# LoRa.net
KiCad netlist of a schematic drawn in EAGLE
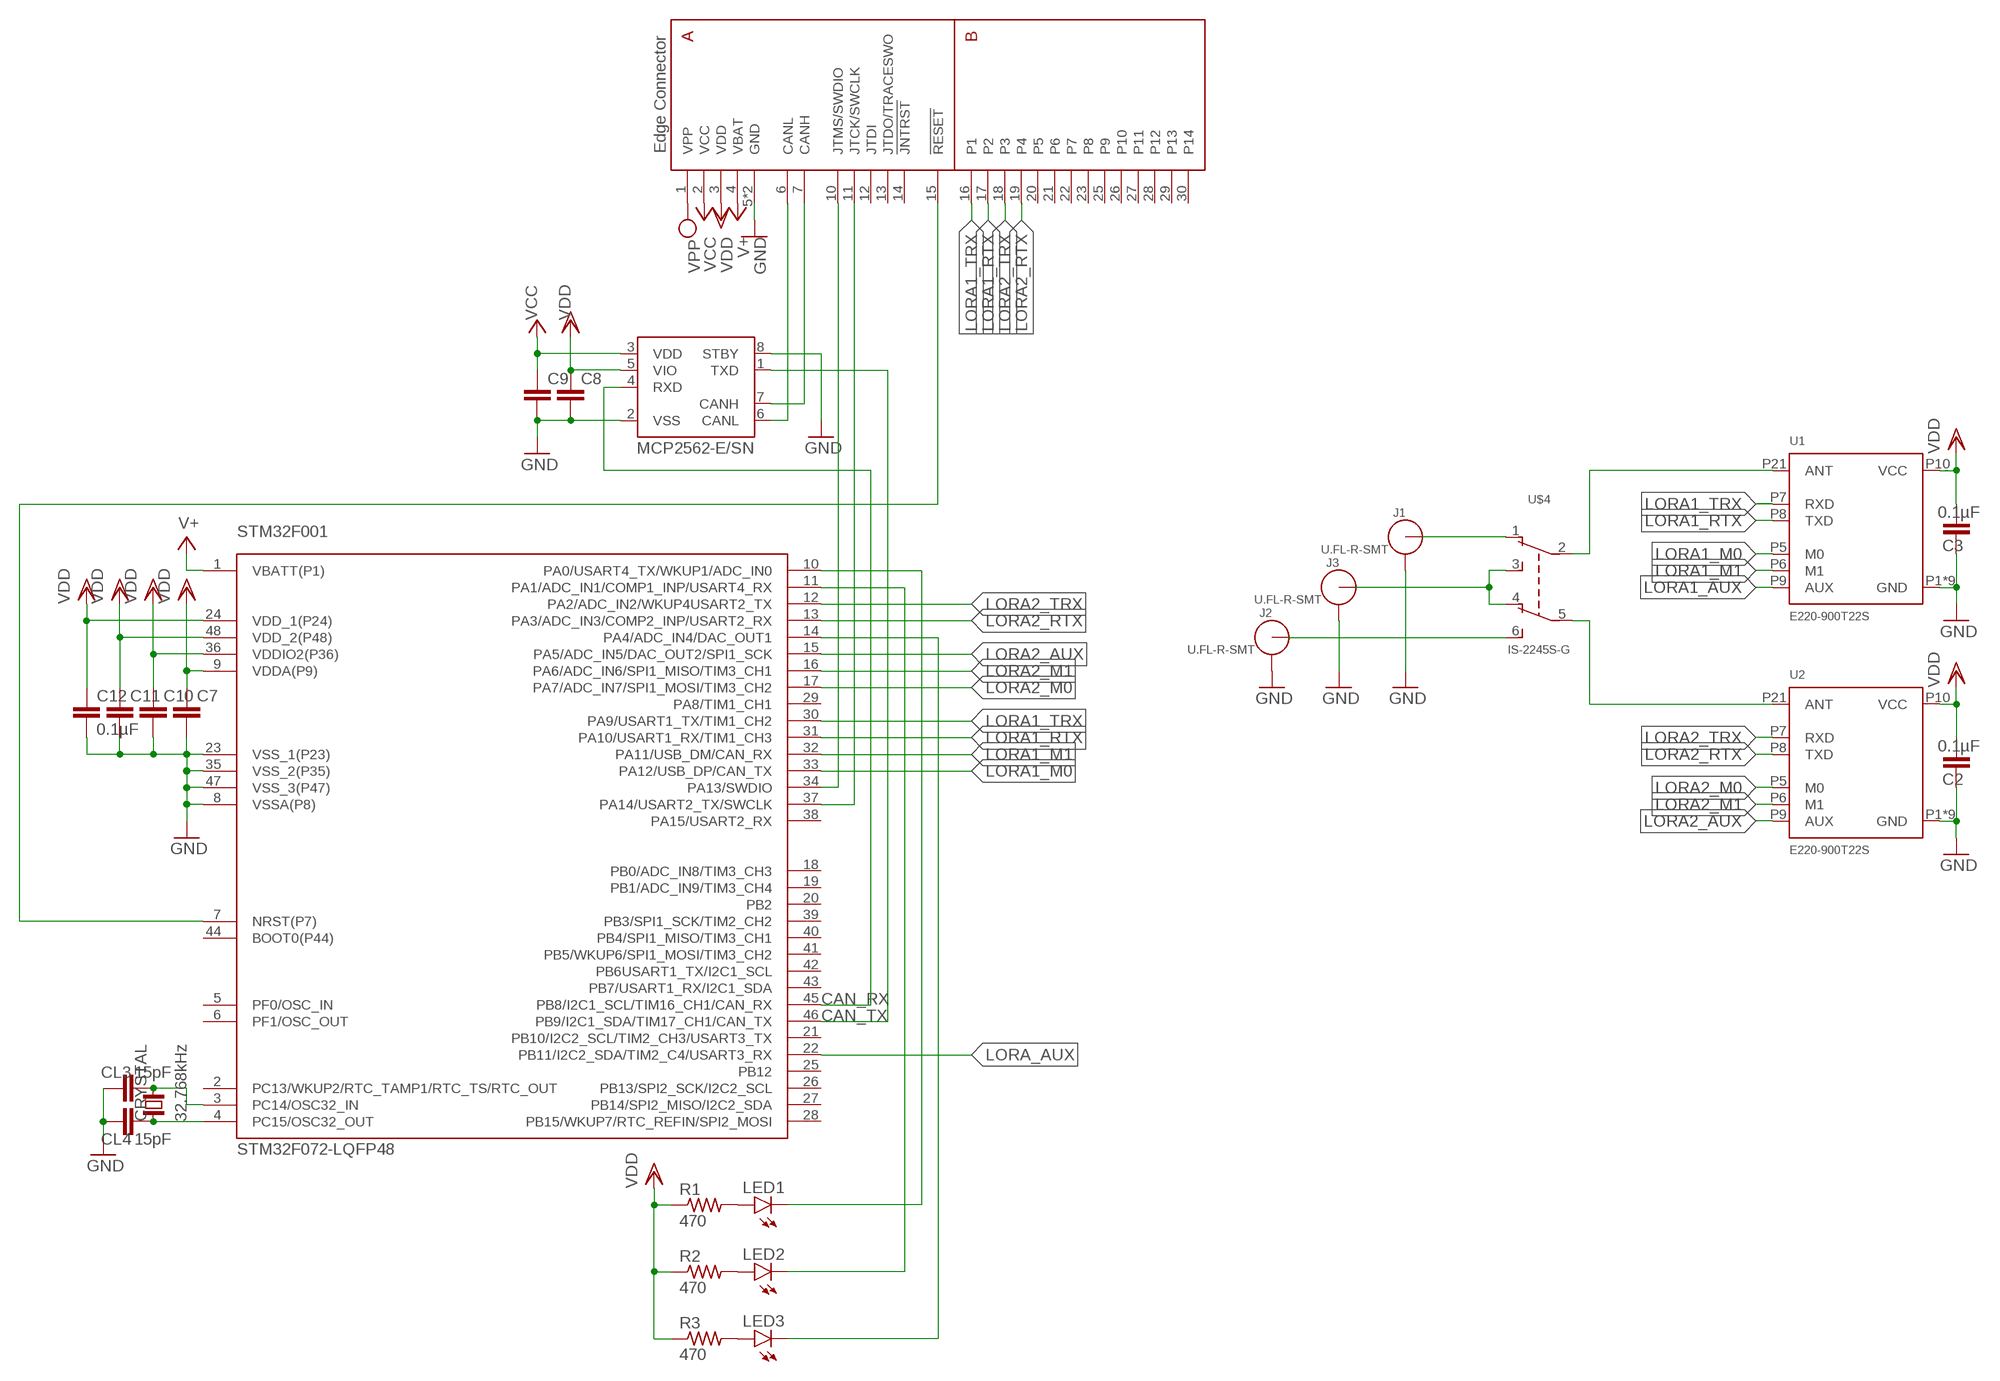
[diagram p0: schematic, sheet 1]

(export (version "E")
  (design (tool "Eeschema 10.0.6"))
  (components
    (comp (ref "C2")
      (value "0.1µF")
      (footprint "eagle-import:C0603K")
      (libsource (lib "eagle-import") (part "C-EUC0603K"))
    )
    (comp (ref "C3")
      (value "0.1µF")
      (footprint "eagle-import:C0603K")
      (libsource (lib "eagle-import") (part "C-EUC0603K"))
    )
    (comp (ref "C7")
      (value "C-EUC0603K")
      (footprint "eagle-import:C0603K")
      (libsource (lib "eagle-import") (part "C-EUC0603K"))
    )
    (comp (ref "C8")
      (value "C-EUC0603K")
      (footprint "eagle-import:C0603K")
      (libsource (lib "eagle-import") (part "C-EUC0603K"))
    )
    (comp (ref "C9")
      (value "C-EUC0603K")
      (footprint "eagle-import:C0603K")
      (libsource (lib "eagle-import") (part "C-EUC0603K"))
    )
    (comp (ref "C10")
      (value "C-EUC0603K")
      (footprint "eagle-import:C0603K")
      (libsource (lib "eagle-import") (part "C-EUC0603K"))
    )
    (comp (ref "C11")
      (value "C-EUC0603K")
      (footprint "eagle-import:C0603K")
      (libsource (lib "eagle-import") (part "C-EUC0603K"))
    )
    (comp (ref "C12")
      (value "0.1µF")
      (footprint "eagle-import:C0603K")
      (libsource (lib "eagle-import") (part "C-EUC0603K"))
    )
    (comp (ref "CL3")
      (value "15pF")
      (footprint "eagle-import:C0603K")
      (libsource (lib "eagle-import") (part "C-EUC0603K"))
    )
    (comp (ref "CL4")
      (value "15pF")
      (footprint "eagle-import:C0603K")
      (libsource (lib "eagle-import") (part "C-EUC0603K"))
    )
    (comp (ref "CRYSTAL")
      (value "32.768kHz")
      (footprint "eagle-import:FC-255")
      (libsource (lib "eagle-import") (part "CRYTALFC-255"))
    )
    (comp (ref "J1")
      (value "U.FL-R-SMT")
      (footprint "eagle-import:U.FL_SMT")
      (fields (field (name "MANUFACTURER") "Hirose") (field (name "MPN") "U.FL-R-SMT-1(01)"))
      (libsource (lib "eagle-import") (part "U.FL-R-SMT"))
    )
    (comp (ref "J2")
      (value "U.FL-R-SMT")
      (footprint "eagle-import:U.FL_SMT")
      (fields (field (name "MANUFACTURER") "Hirose") (field (name "MPN") "U.FL-R-SMT-1(01)"))
      (libsource (lib "eagle-import") (part "U.FL-R-SMT"))
    )
    (comp (ref "J3")
      (value "U.FL-R-SMT")
      (footprint "eagle-import:U.FL_SMT")
      (fields (field (name "MANUFACTURER") "Hirose") (field (name "MPN") "U.FL-R-SMT-1(01)"))
      (libsource (lib "eagle-import") (part "U.FL-R-SMT"))
    )
    (comp (ref "LED1")
      (value "LEDCHIP-LED0603")
      (footprint "eagle-import:CHIP-LED0603")
      (libsource (lib "eagle-import") (part "LEDCHIP-LED0603"))
    )
    (comp (ref "LED2")
      (value "LEDCHIP-LED0603")
      (footprint "eagle-import:CHIP-LED0603")
      (libsource (lib "eagle-import") (part "LEDCHIP-LED0603"))
    )
    (comp (ref "LED3")
      (value "LEDCHIP-LED0603")
      (footprint "eagle-import:CHIP-LED0603")
      (libsource (lib "eagle-import") (part "LEDCHIP-LED0603"))
    )
    (comp (ref "MCP1")
      (value "MCP2562-E/SN")
      (footprint "eagle-import:SOIC127P600X175-8N")
      (fields (field (name "MF") "Microchip"))
      (libsource (lib "eagle-import") (part "MCP2562-E/SN"))
    )
    (comp (ref "R1")
      (value "470")
      (footprint "eagle-import:R0603")
      (libsource (lib "eagle-import") (part "R-US_R0603"))
    )
    (comp (ref "R2")
      (value "470")
      (footprint "eagle-import:R0603")
      (libsource (lib "eagle-import") (part "R-US_R0603"))
    )
    (comp (ref "R3")
      (value "470")
      (footprint "eagle-import:R0603")
      (libsource (lib "eagle-import") (part "R-US_R0603"))
    )
    (comp (ref "STM32F001")
      (value "STM32F072-LQFP48")
      (footprint "eagle-import:LQFP48")
      (libsource (lib "eagle-import") (part "STM32F072-LQFP48"))
    )
    (comp (ref "U$2")
      (value "EDGE30")
      (footprint "eagle-import:EDGE30")
      (libsource (lib "eagle-import") (part "EDGE30"))
    )
    (comp (ref "U$4")
      (value "IS-2245S-G")
      (footprint "eagle-import:IS-2245S-G")
      (libsource (lib "eagle-import") (part "IS-2245S-G"))
    )
    (comp (ref "U1")
      (value "E220-900T22S")
      (footprint "eagle-import:E220-900T22S")
      (libsource (lib "eagle-import") (part "E220-900T22S"))
    )
    (comp (ref "U2")
      (value "E220-900T22S")
      (footprint "eagle-import:E220-900T22S")
      (libsource (lib "eagle-import") (part "E220-900T22S"))
    )
  )
  (nets
    (net (code "1") (name "/CAN_RX") (class "Default")
      (node (ref "MCP1") (pin "4") (pinfunction "RXD_4") (pintype "output"))
      (node (ref "STM32F001") (pin "45") (pinfunction "PB8/I2C1_SCL/TIM16_CH1/CAN_RX_45") (pintype "bidirectional"))
    )
    (net (code "2") (name "/CAN_TX") (class "Default")
      (node (ref "MCP1") (pin "1") (pinfunction "TXD_1") (pintype "input"))
      (node (ref "STM32F001") (pin "46") (pinfunction "PB9/I2C1_SDA/TIM17_CH1/CAN_TX_46") (pintype "bidirectional"))
    )
    (net (code "3") (name "GND") (class "Default")
      (node (ref "C10") (pin "2") (pinfunction "2_2") (pintype "passive"))
      (node (ref "C11") (pin "2") (pinfunction "2_2") (pintype "passive"))
      (node (ref "C12") (pin "2") (pinfunction "2_2") (pintype "passive"))
      (node (ref "C2") (pin "1") (pinfunction "1_1") (pintype "passive"))
      (node (ref "C3") (pin "1") (pinfunction "1_1") (pintype "passive"))
      (node (ref "C7") (pin "2") (pinfunction "2_2") (pintype "passive"))
      (node (ref "C8") (pin "2") (pinfunction "2_2") (pintype "passive"))
      (node (ref "C9") (pin "2") (pinfunction "2_2") (pintype "passive"))
      (node (ref "CL3") (pin "1") (pinfunction "1_1") (pintype "passive"))
      (node (ref "CL4") (pin "1") (pinfunction "1_1") (pintype "passive"))
      (node (ref "J1") (pin "GND1") (pinfunction "P$2_GND1") (pintype "bidirectional"))
      (node (ref "J1") (pin "GND2") (pinfunction "P$2_GND2") (pintype "bidirectional"))
      (node (ref "J2") (pin "GND1") (pinfunction "P$2_GND1") (pintype "bidirectional"))
      (node (ref "J2") (pin "GND2") (pinfunction "P$2_GND2") (pintype "bidirectional"))
      (node (ref "J3") (pin "GND1") (pinfunction "P$2_GND1") (pintype "bidirectional"))
      (node (ref "J3") (pin "GND2") (pinfunction "P$2_GND2") (pintype "bidirectional"))
      (node (ref "MCP1") (pin "2") (pinfunction "VSS_2") (pintype "power_in"))
      (node (ref "MCP1") (pin "8") (pinfunction "STBY_8") (pintype "input"))
      (node (ref "STM32F001") (pin "23") (pinfunction "VSS_1(P23)_23") (pintype "bidirectional"))
      (node (ref "STM32F001") (pin "35") (pinfunction "VSS_2(P35)_35") (pintype "bidirectional"))
      (node (ref "STM32F001") (pin "47") (pinfunction "VSS_3(P47)_47") (pintype "bidirectional"))
      (node (ref "STM32F001") (pin "8") (pinfunction "VSSA(P8)_8") (pintype "bidirectional"))
      (node (ref "U$2") (pin "5") (pinfunction "GND_5") (pintype "power_in"))
      (node (ref "U$2") (pin "8") (pinfunction "GND_8") (pintype "power_in"))
      (node (ref "U1") (pin "P1") (pinfunction "GND_P1") (pintype "bidirectional"))
      (node (ref "U1") (pin "P11") (pinfunction "GND_P11") (pintype "bidirectional"))
      (node (ref "U1") (pin "P13") (pinfunction "GND_P13") (pintype "bidirectional"))
      (node (ref "U1") (pin "P19") (pinfunction "GND_P19") (pintype "bidirectional"))
      (node (ref "U1") (pin "P2") (pinfunction "GND_P2") (pintype "bidirectional"))
      (node (ref "U1") (pin "P20") (pinfunction "GND_P20") (pintype "bidirectional"))
      (node (ref "U1") (pin "P22") (pinfunction "GND_P22") (pintype "bidirectional"))
      (node (ref "U1") (pin "P3") (pinfunction "GND_P3") (pintype "bidirectional"))
      (node (ref "U1") (pin "P4") (pinfunction "GND_P4") (pintype "bidirectional"))
      (node (ref "U2") (pin "P1") (pinfunction "GND_P1") (pintype "bidirectional"))
      (node (ref "U2") (pin "P11") (pinfunction "GND_P11") (pintype "bidirectional"))
      (node (ref "U2") (pin "P13") (pinfunction "GND_P13") (pintype "bidirectional"))
      (node (ref "U2") (pin "P19") (pinfunction "GND_P19") (pintype "bidirectional"))
      (node (ref "U2") (pin "P2") (pinfunction "GND_P2") (pintype "bidirectional"))
      (node (ref "U2") (pin "P20") (pinfunction "GND_P20") (pintype "bidirectional"))
      (node (ref "U2") (pin "P22") (pinfunction "GND_P22") (pintype "bidirectional"))
      (node (ref "U2") (pin "P3") (pinfunction "GND_P3") (pintype "bidirectional"))
      (node (ref "U2") (pin "P4") (pinfunction "GND_P4") (pintype "bidirectional"))
    )
    (net (code "4") (name "LORA1_AUX") (class "Default")
      (node (ref "U1") (pin "P9") (pinfunction "AUX_P9") (pintype "bidirectional"))
    )
    (net (code "5") (name "LORA1_M0") (class "Default")
      (node (ref "STM32F001") (pin "33") (pinfunction "PA12/USB_DP/CAN_TX_33") (pintype "bidirectional"))
      (node (ref "U1") (pin "P5") (pinfunction "M0_P5") (pintype "bidirectional"))
    )
    (net (code "6") (name "LORA1_M1") (class "Default")
      (node (ref "STM32F001") (pin "32") (pinfunction "PA11/USB_DM/CAN_RX_32") (pintype "bidirectional"))
      (node (ref "U1") (pin "P6") (pinfunction "M1_P6") (pintype "bidirectional"))
    )
    (net (code "7") (name "LORA1_RTX") (class "Default")
      (node (ref "STM32F001") (pin "31") (pinfunction "PA10/USART1_RX/TIM1_CH3_31") (pintype "bidirectional"))
      (node (ref "U$2") (pin "17") (pinfunction "P2_17") (pintype "bidirectional"))
      (node (ref "U1") (pin "P8") (pinfunction "TXD_P8") (pintype "bidirectional"))
    )
    (net (code "8") (name "LORA1_TRX") (class "Default")
      (node (ref "STM32F001") (pin "30") (pinfunction "PA9/USART1_TX/TIM1_CH2_30") (pintype "bidirectional"))
      (node (ref "U$2") (pin "16") (pinfunction "P1_16") (pintype "bidirectional"))
      (node (ref "U1") (pin "P7") (pinfunction "RXD_P7") (pintype "bidirectional"))
    )
    (net (code "9") (name "LORA2_AUX") (class "Default")
      (node (ref "STM32F001") (pin "15") (pinfunction "PA5/ADC_IN5/DAC_OUT2/SPI1_SCK_15") (pintype "bidirectional"))
      (node (ref "U2") (pin "P9") (pinfunction "AUX_P9") (pintype "bidirectional"))
    )
    (net (code "10") (name "LORA2_M0") (class "Default")
      (node (ref "STM32F001") (pin "17") (pinfunction "PA7/ADC_IN7/SPI1_MOSI/TIM3_CH2_17") (pintype "bidirectional"))
      (node (ref "U2") (pin "P5") (pinfunction "M0_P5") (pintype "bidirectional"))
    )
    (net (code "11") (name "LORA2_M1") (class "Default")
      (node (ref "STM32F001") (pin "16") (pinfunction "PA6/ADC_IN6/SPI1_MISO/TIM3_CH1_16") (pintype "bidirectional"))
      (node (ref "U2") (pin "P6") (pinfunction "M1_P6") (pintype "bidirectional"))
    )
    (net (code "12") (name "LORA2_RTX") (class "Default")
      (node (ref "STM32F001") (pin "13") (pinfunction "PA3/ADC_IN3/COMP2_INP/USART2_RX_13") (pintype "bidirectional"))
      (node (ref "U$2") (pin "19") (pinfunction "P4_19") (pintype "bidirectional"))
      (node (ref "U2") (pin "P8") (pinfunction "TXD_P8") (pintype "bidirectional"))
    )
    (net (code "13") (name "LORA2_TRX") (class "Default")
      (node (ref "STM32F001") (pin "12") (pinfunction "PA2/ADC_IN2/WKUP4USART2_TX_12") (pintype "bidirectional"))
      (node (ref "U$2") (pin "18") (pinfunction "P3_18") (pintype "bidirectional"))
      (node (ref "U2") (pin "P7") (pinfunction "RXD_P7") (pintype "bidirectional"))
    )
    (net (code "14") (name "LORA_AUX") (class "Default")
      (node (ref "STM32F001") (pin "22") (pinfunction "PB11/I2C2_SDA/TIM2_C4/USART3_RX_22") (pintype "bidirectional"))
    )
    (net (code "15") (name "Net-(J1-ANT)") (class "Default")
      (node (ref "J1") (pin "SIG") (pinfunction "ANT_SIG") (pintype "bidirectional"))
      (node (ref "U$4") (pin "1") (pinfunction "1_1") (pintype "passive"))
    )
    (net (code "16") (name "Net-(J2-ANT)") (class "Default")
      (node (ref "J2") (pin "SIG") (pinfunction "ANT_SIG") (pintype "bidirectional"))
      (node (ref "U$4") (pin "6") (pinfunction "6_6") (pintype "passive"))
    )
    (net (code "17") (name "Net-(J3-ANT)") (class "Default")
      (node (ref "J3") (pin "SIG") (pinfunction "ANT_SIG") (pintype "bidirectional"))
      (node (ref "U$4") (pin "3") (pinfunction "3_3") (pintype "passive"))
      (node (ref "U$4") (pin "4") (pinfunction "4_4") (pintype "passive"))
    )
    (net (code "18") (name "Net-(LED1-PadA)") (class "Default")
      (node (ref "LED1") (pin "A") (pinfunction "A_A") (pintype "passive"))
      (node (ref "R1") (pin "2") (pinfunction "2_2") (pintype "passive"))
    )
    (net (code "19") (name "Net-(LED2-PadA)") (class "Default")
      (node (ref "LED2") (pin "A") (pinfunction "A_A") (pintype "passive"))
      (node (ref "R2") (pin "2") (pinfunction "2_2") (pintype "passive"))
    )
    (net (code "20") (name "Net-(LED3-PadA)") (class "Default")
      (node (ref "LED3") (pin "A") (pinfunction "A_A") (pintype "passive"))
      (node (ref "R3") (pin "2") (pinfunction "2_2") (pintype "passive"))
    )
    (net (code "21") (name "Net-(MCP1-CANH)") (class "Default")
      (node (ref "MCP1") (pin "7") (pinfunction "CANH_7") (pintype "input"))
      (node (ref "U$2") (pin "7") (pinfunction "CANH_7") (pintype "bidirectional"))
    )
    (net (code "22") (name "Net-(MCP1-CANL)") (class "Default")
      (node (ref "MCP1") (pin "6") (pinfunction "CANL_6") (pintype "input"))
      (node (ref "U$2") (pin "6") (pinfunction "CANL_6") (pintype "bidirectional"))
    )
    (net (code "23") (name "Net-(STM32F001-NRST(P7))") (class "Default")
      (node (ref "STM32F001") (pin "7") (pinfunction "NRST(P7)_7") (pintype "bidirectional"))
      (node (ref "U$2") (pin "15") (pinfunction "~{RESET}_15") (pintype "bidirectional"))
    )
    (net (code "24") (name "Net-(STM32F001-PA0{slash}USART4_TX{slash}WKUP1{slash}ADC_IN0)") (class "Default")
      (node (ref "LED1") (pin "C") (pinfunction "C_C") (pintype "passive"))
      (node (ref "STM32F001") (pin "10") (pinfunction "PA0/USART4_TX/WKUP1/ADC_IN0_10") (pintype "bidirectional"))
    )
    (net (code "25") (name "Net-(STM32F001-PA1{slash}ADC_IN1{slash}COMP1_INP{slash}USART4_RX)") (class "Default")
      (node (ref "LED2") (pin "C") (pinfunction "C_C") (pintype "passive"))
      (node (ref "STM32F001") (pin "11") (pinfunction "PA1/ADC_IN1/COMP1_INP/USART4_RX_11") (pintype "bidirectional"))
    )
    (net (code "26") (name "Net-(STM32F001-PA4{slash}ADC_IN4{slash}DAC_OUT1)") (class "Default")
      (node (ref "LED3") (pin "C") (pinfunction "C_C") (pintype "passive"))
      (node (ref "STM32F001") (pin "14") (pinfunction "PA4/ADC_IN4/DAC_OUT1_14") (pintype "bidirectional"))
    )
    (net (code "27") (name "Net-(STM32F001-PA13{slash}SWDIO)") (class "Default")
      (node (ref "STM32F001") (pin "34") (pinfunction "PA13/SWDIO_34") (pintype "bidirectional"))
      (node (ref "U$2") (pin "10") (pinfunction "JTMS/SWDIO_10") (pintype "bidirectional"))
    )
    (net (code "28") (name "Net-(STM32F001-PA14{slash}USART2_TX{slash}SWCLK)") (class "Default")
      (node (ref "STM32F001") (pin "37") (pinfunction "PA14/USART2_TX/SWCLK_37") (pintype "bidirectional"))
      (node (ref "U$2") (pin "11") (pinfunction "JTCK/SWCLK_11") (pintype "bidirectional"))
    )
    (net (code "29") (name "Net-(STM32F001-PC14{slash}OSC32_IN)") (class "Default")
      (node (ref "CL3") (pin "2") (pinfunction "2_2") (pintype "passive"))
      (node (ref "CRYSTAL") (pin "2") (pinfunction "2_2") (pintype "passive"))
      (node (ref "STM32F001") (pin "3") (pinfunction "PC14/OSC32_IN_3") (pintype "bidirectional"))
    )
    (net (code "30") (name "Net-(STM32F001-PC15{slash}OSC32_OUT)") (class "Default")
      (node (ref "CL4") (pin "2") (pinfunction "2_2") (pintype "passive"))
      (node (ref "CRYSTAL") (pin "1") (pinfunction "1_1") (pintype "passive"))
      (node (ref "STM32F001") (pin "4") (pinfunction "PC15/OSC32_OUT_4") (pintype "bidirectional"))
    )
    (net (code "31") (name "Net-(U1-ANT)") (class "Default")
      (node (ref "U$4") (pin "2") (pinfunction "2_2") (pintype "passive"))
      (node (ref "U1") (pin "P21") (pinfunction "ANT_P21") (pintype "bidirectional"))
    )
    (net (code "32") (name "Net-(U2-ANT)") (class "Default")
      (node (ref "U$4") (pin "5") (pinfunction "5_5") (pintype "passive"))
      (node (ref "U2") (pin "P21") (pinfunction "ANT_P21") (pintype "bidirectional"))
    )
    (net (code "33") (name "V+") (class "Default")
      (node (ref "STM32F001") (pin "1") (pinfunction "VBATT(P1)_1") (pintype "bidirectional"))
      (node (ref "U$2") (pin "4") (pinfunction "VBAT_4") (pintype "power_in"))
    )
    (net (code "34") (name "VCC") (class "Default")
      (node (ref "C9") (pin "1") (pinfunction "1_1") (pintype "passive"))
      (node (ref "MCP1") (pin "3") (pinfunction "VDD_3") (pintype "power_in"))
      (node (ref "U$2") (pin "2") (pinfunction "VCC_2") (pintype "power_in"))
    )
    (net (code "35") (name "VDD") (class "Default")
      (node (ref "C10") (pin "1") (pinfunction "1_1") (pintype "passive"))
      (node (ref "C11") (pin "1") (pinfunction "1_1") (pintype "passive"))
      (node (ref "C12") (pin "1") (pinfunction "1_1") (pintype "passive"))
      (node (ref "C2") (pin "2") (pinfunction "2_2") (pintype "passive"))
      (node (ref "C3") (pin "2") (pinfunction "2_2") (pintype "passive"))
      (node (ref "C7") (pin "1") (pinfunction "1_1") (pintype "passive"))
      (node (ref "C8") (pin "1") (pinfunction "1_1") (pintype "passive"))
      (node (ref "MCP1") (pin "5") (pinfunction "VIO_5") (pintype "power_in"))
      (node (ref "R1") (pin "1") (pinfunction "1_1") (pintype "passive"))
      (node (ref "R2") (pin "1") (pinfunction "1_1") (pintype "passive"))
      (node (ref "R3") (pin "1") (pinfunction "1_1") (pintype "passive"))
      (node (ref "STM32F001") (pin "24") (pinfunction "VDD_1(P24)_24") (pintype "bidirectional"))
      (node (ref "STM32F001") (pin "36") (pinfunction "VDDIO2(P36)_36") (pintype "bidirectional"))
      (node (ref "STM32F001") (pin "48") (pinfunction "VDD_2(P48)_48") (pintype "bidirectional"))
      (node (ref "STM32F001") (pin "9") (pinfunction "VDDA(P9)_9") (pintype "bidirectional"))
      (node (ref "U$2") (pin "3") (pinfunction "VDD_3") (pintype "power_in"))
      (node (ref "U1") (pin "P10") (pinfunction "VCC_P10") (pintype "bidirectional"))
      (node (ref "U2") (pin "P10") (pinfunction "VCC_P10") (pintype "bidirectional"))
    )
    (net (code "36") (name "VPP") (class "Default")
      (node (ref "U$2") (pin "1") (pinfunction "VPP_1") (pintype "power_in"))
    )
    (net (code "37") (name "unconnected-(STM32F001-BOOT0(P44)-Pad44)") (class "Default")
      (node (ref "STM32F001") (pin "44") (pinfunction "BOOT0(P44)_44") (pintype "bidirectional"))
    )
    (net (code "38") (name "unconnected-(STM32F001-PA8{slash}TIM1_CH1-Pad29)") (class "Default")
      (node (ref "STM32F001") (pin "29") (pinfunction "PA8/TIM1_CH1_29") (pintype "bidirectional"))
    )
    (net (code "39") (name "unconnected-(STM32F001-PA15{slash}USART2_RX-Pad38)") (class "Default")
      (node (ref "STM32F001") (pin "38") (pinfunction "PA15/USART2_RX_38") (pintype "bidirectional"))
    )
    (net (code "40") (name "unconnected-(STM32F001-PB0{slash}ADC_IN8{slash}TIM3_CH3-Pad18)") (class "Default")
      (node (ref "STM32F001") (pin "18") (pinfunction "PB0/ADC_IN8/TIM3_CH3_18") (pintype "bidirectional"))
    )
    (net (code "41") (name "unconnected-(STM32F001-PB1{slash}ADC_IN9{slash}TIM3_CH4-Pad19)") (class "Default")
      (node (ref "STM32F001") (pin "19") (pinfunction "PB1/ADC_IN9/TIM3_CH4_19") (pintype "bidirectional"))
    )
    (net (code "42") (name "unconnected-(STM32F001-PB2-Pad20)") (class "Default")
      (node (ref "STM32F001") (pin "20") (pinfunction "PB2_20") (pintype "bidirectional"))
    )
    (net (code "43") (name "unconnected-(STM32F001-PB3{slash}SPI1_SCK{slash}TIM2_CH2-Pad39)") (class "Default")
      (node (ref "STM32F001") (pin "39") (pinfunction "PB3/SPI1_SCK/TIM2_CH2_39") (pintype "bidirectional"))
    )
    (net (code "44") (name "unconnected-(STM32F001-PB4{slash}SPI1_MISO{slash}TIM3_CH1-Pad40)") (class "Default")
      (node (ref "STM32F001") (pin "40") (pinfunction "PB4/SPI1_MISO/TIM3_CH1_40") (pintype "bidirectional"))
    )
    (net (code "45") (name "unconnected-(STM32F001-PB5{slash}WKUP6{slash}SPI1_MOSI{slash}TIM3_CH2-Pad41)") (class "Default")
      (node (ref "STM32F001") (pin "41") (pinfunction "PB5/WKUP6/SPI1_MOSI/TIM3_CH2_41") (pintype "bidirectional"))
    )
    (net (code "46") (name "unconnected-(STM32F001-PB6USART1_TX{slash}I2C1_SCL-Pad42)") (class "Default")
      (node (ref "STM32F001") (pin "42") (pinfunction "PB6USART1_TX/I2C1_SCL_42") (pintype "bidirectional"))
    )
    (net (code "47") (name "unconnected-(STM32F001-PB7{slash}USART1_RX{slash}I2C1_SDA-Pad43)") (class "Default")
      (node (ref "STM32F001") (pin "43") (pinfunction "PB7/USART1_RX/I2C1_SDA_43") (pintype "bidirectional"))
    )
    (net (code "48") (name "unconnected-(STM32F001-PB10{slash}I2C2_SCL{slash}TIM2_CH3{slash}USART3_TX-Pad21)") (class "Default")
      (node (ref "STM32F001") (pin "21") (pinfunction "PB10/I2C2_SCL/TIM2_CH3/USART3_TX_21") (pintype "bidirectional"))
    )
    (net (code "49") (name "unconnected-(STM32F001-PB12-Pad25)") (class "Default")
      (node (ref "STM32F001") (pin "25") (pinfunction "PB12_25") (pintype "bidirectional"))
    )
    (net (code "50") (name "unconnected-(STM32F001-PB13{slash}SPI2_SCK{slash}I2C2_SCL-Pad26)") (class "Default")
      (node (ref "STM32F001") (pin "26") (pinfunction "PB13/SPI2_SCK/I2C2_SCL_26") (pintype "bidirectional"))
    )
    (net (code "51") (name "unconnected-(STM32F001-PB14{slash}SPI2_MISO{slash}I2C2_SDA-Pad27)") (class "Default")
      (node (ref "STM32F001") (pin "27") (pinfunction "PB14/SPI2_MISO/I2C2_SDA_27") (pintype "bidirectional"))
    )
    (net (code "52") (name "unconnected-(STM32F001-PB15{slash}WKUP7{slash}RTC_REFIN{slash}SPI2_MOSI-Pad28)") (class "Default")
      (node (ref "STM32F001") (pin "28") (pinfunction "PB15/WKUP7/RTC_REFIN/SPI2_MOSI_28") (pintype "bidirectional"))
    )
    (net (code "53") (name "unconnected-(STM32F001-PC13{slash}WKUP2{slash}RTC_TAMP1{slash}RTC_TS{slash}RTC_OUT-Pad2)") (class "Default")
      (node (ref "STM32F001") (pin "2") (pinfunction "PC13/WKUP2/RTC_TAMP1/RTC_TS/RTC_OUT_2") (pintype "bidirectional"))
    )
    (net (code "54") (name "unconnected-(STM32F001-PF0{slash}OSC_IN-Pad5)") (class "Default")
      (node (ref "STM32F001") (pin "5") (pinfunction "PF0/OSC_IN_5") (pintype "bidirectional"))
    )
    (net (code "55") (name "unconnected-(STM32F001-PF1{slash}OSC_OUT-Pad6)") (class "Default")
      (node (ref "STM32F001") (pin "6") (pinfunction "PF1/OSC_OUT_6") (pintype "bidirectional"))
    )
    (net (code "56") (name "unconnected-(U$2-JTDI-Pad12)") (class "Default")
      (node (ref "U$2") (pin "12") (pinfunction "JTDI_12") (pintype "bidirectional"))
    )
    (net (code "57") (name "unconnected-(U$2-JTDO{slash}TRACESWO-Pad13)") (class "Default")
      (node (ref "U$2") (pin "13") (pinfunction "JTDO/TRACESWO_13") (pintype "bidirectional"))
    )
    (net (code "58") (name "unconnected-(U$2-P5-Pad20)") (class "Default")
      (node (ref "U$2") (pin "20") (pinfunction "P5_20") (pintype "bidirectional"))
    )
    (net (code "59") (name "unconnected-(U$2-P6-Pad21)") (class "Default")
      (node (ref "U$2") (pin "21") (pinfunction "P6_21") (pintype "bidirectional"))
    )
    (net (code "60") (name "unconnected-(U$2-P7-Pad22)") (class "Default")
      (node (ref "U$2") (pin "22") (pinfunction "P7_22") (pintype "bidirectional"))
    )
    (net (code "61") (name "unconnected-(U$2-P8-Pad23)") (class "Default")
      (node (ref "U$2") (pin "23") (pinfunction "P8_23") (pintype "bidirectional"))
    )
    (net (code "62") (name "unconnected-(U$2-P9-Pad25)") (class "Default")
      (node (ref "U$2") (pin "25") (pinfunction "P9_25") (pintype "bidirectional"))
    )
    (net (code "63") (name "unconnected-(U$2-P10-Pad26)") (class "Default")
      (node (ref "U$2") (pin "26") (pinfunction "P10_26") (pintype "bidirectional"))
    )
    (net (code "64") (name "unconnected-(U$2-P11-Pad27)") (class "Default")
      (node (ref "U$2") (pin "27") (pinfunction "P11_27") (pintype "bidirectional"))
    )
    (net (code "65") (name "unconnected-(U$2-P12-Pad28)") (class "Default")
      (node (ref "U$2") (pin "28") (pinfunction "P12_28") (pintype "bidirectional"))
    )
    (net (code "66") (name "unconnected-(U$2-P13-Pad29)") (class "Default")
      (node (ref "U$2") (pin "29") (pinfunction "P13_29") (pintype "bidirectional"))
    )
    (net (code "67") (name "unconnected-(U$2-P14-Pad30)") (class "Default")
      (node (ref "U$2") (pin "30") (pinfunction "P14_30") (pintype "bidirectional"))
    )
    (net (code "68") (name "unconnected-(U$2-~{JNTRST}-Pad14)") (class "Default")
      (node (ref "U$2") (pin "14") (pinfunction "~{JNTRST}_14") (pintype "bidirectional"))
    )
  )
)
